# EFM8_Tag-Connect.net
KiCad netlist of a schematic drawn in EAGLE
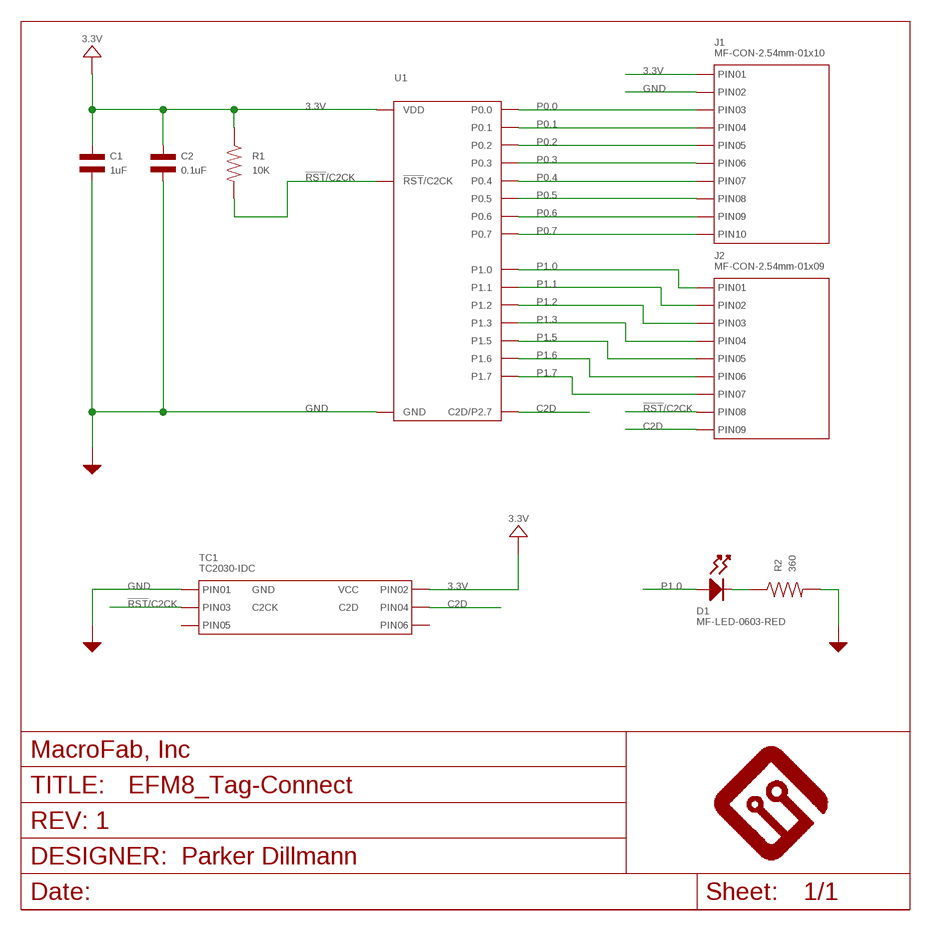
[diagram p0: schematic, sheet 1]

(export (version "E")
  (design (tool "Eeschema 10.0.6"))
  (components
    (comp (ref "C1")
      (value "1uF")
      (footprint "eagle-import:C0402")
      (fields (field (name "MPN") "MF-CAP-0402-1uF"))
      (libsource (lib "eagle-import") (part "CAPACITOR_NP_0402"))
    )
    (comp (ref "C2")
      (value "0.1uF")
      (footprint "eagle-import:C0402")
      (fields (field (name "MPN") "MF-CAP-0402-0.1uF"))
      (libsource (lib "eagle-import") (part "CAPACITOR_NP_0402"))
    )
    (comp (ref "D1")
      (value "MF-LED-0603-RED")
      (footprint "eagle-import:LED0603")
      (fields (field (name "HOUSEPART") "YES"))
      (libsource (lib "eagle-import") (part "LED_SINGLE-0603-RED"))
    )
    (comp (ref "FRAME1")
      (value "MF_FRAMEDEFAULT")
      (footprint "eagle-import:MF_FRAME_DEFAULT")
      (fields
        (field (name "HOUSEPART") "0")
        (field (name "DNAME") "Parker Dillmann")
        (field (name "REVNUM") "REV: 1")
      )
      (libsource (lib "eagle-import") (part "MF_FRAMEDEFAULT"))
    )
    (comp (ref "J1")
      (value "MF-CON-2.54mm-01x10")
      (footprint "eagle-import:PTH_2.54MM_01X10")
      (fields (field (name "HOUSEPART") "YES"))
      (libsource (lib "eagle-import") (part "CON_01X10_PTH_2.54MM"))
    )
    (comp (ref "J2")
      (value "MF-CON-2.54mm-01x09")
      (footprint "eagle-import:PTH_2.54MM_01X09")
      (fields (field (name "HOUSEPART") "YES"))
      (libsource (lib "eagle-import") (part "CON_01X09_PTH_2.54MM"))
    )
    (comp (ref "R1")
      (value "10K")
      (footprint "eagle-import:R0402")
      (fields (field (name "MPN") "MF-RES-0402-10K"))
      (libsource (lib "eagle-import") (part "RESISTOR_0402"))
    )
    (comp (ref "R2")
      (value "360")
      (footprint "eagle-import:R0402")
      (fields (field (name "MPN") "MF-RES-0402-360"))
      (libsource (lib "eagle-import") (part "RESISTOR_0402"))
    )
    (comp (ref "TC1")
      (value "TC2030-IDC")
      (footprint "eagle-import:TC2030-IDC-FP")
      (fields (field (name "HOUSEPART") "NO"))
      (libsource (lib "eagle-import") (part "CON_02X03_TC2030-IDC_SILABS2TC"))
    )
    (comp (ref "U1")
      (value "EFM8BB10F(2/4/8)G-A-QFN20")
      (footprint "eagle-import:EFM8BB10F(2_4_8)G-A-QFN20")
      (fields (field (name "HOUSEPART") "NO") (field (name "MPN") "EFM8BB10F2G-A-QFN20"))
      (libsource (lib "eagle-import") (part "EFM8BB10F(2/4/8)G-A-QFN20"))
    )
  )
  (nets
    (net (code "1") (name "/C2D") (class "Default")
      (node (ref "J2") (pin "P$9") (pinfunction "PIN9_P$9") (pintype "bidirectional"))
      (node (ref "TC1") (pin "P$4") (pinfunction "PIN4_P$4") (pintype "bidirectional"))
      (node (ref "U1") (pin "P$6") (pinfunction "C2D/P2.7_P$6") (pintype "bidirectional"))
    )
    (net (code "2") (name "/P0.0") (class "Default")
      (node (ref "J1") (pin "P$3") (pinfunction "PIN3_P$3") (pintype "bidirectional"))
      (node (ref "U1") (pin "P$2") (pinfunction "P0.0_P$2") (pintype "bidirectional"))
    )
    (net (code "3") (name "/P0.1") (class "Default")
      (node (ref "J1") (pin "P$4") (pinfunction "PIN4_P$4") (pintype "bidirectional"))
      (node (ref "U1") (pin "P$1") (pinfunction "P0.1_P$1") (pintype "bidirectional"))
    )
    (net (code "4") (name "/P0.2") (class "Default")
      (node (ref "J1") (pin "P$5") (pinfunction "PIN5_P$5") (pintype "bidirectional"))
      (node (ref "U1") (pin "P$20") (pinfunction "P0.2_P$20") (pintype "bidirectional"))
    )
    (net (code "5") (name "/P0.3") (class "Default")
      (node (ref "J1") (pin "P$6") (pinfunction "PIN6_P$6") (pintype "bidirectional"))
      (node (ref "U1") (pin "P$19") (pinfunction "P0.3_P$19") (pintype "bidirectional"))
    )
    (net (code "6") (name "/P0.4") (class "Default")
      (node (ref "J1") (pin "P$7") (pinfunction "PIN7_P$7") (pintype "bidirectional"))
      (node (ref "U1") (pin "P$18") (pinfunction "P0.4_P$18") (pintype "bidirectional"))
    )
    (net (code "7") (name "/P0.5") (class "Default")
      (node (ref "J1") (pin "P$8") (pinfunction "PIN8_P$8") (pintype "bidirectional"))
      (node (ref "U1") (pin "P$17") (pinfunction "P0.5_P$17") (pintype "bidirectional"))
    )
    (net (code "8") (name "/P0.6") (class "Default")
      (node (ref "J1") (pin "P$9") (pinfunction "PIN9_P$9") (pintype "bidirectional"))
      (node (ref "U1") (pin "P$16") (pinfunction "P0.6_P$16") (pintype "bidirectional"))
    )
    (net (code "9") (name "/P0.7") (class "Default")
      (node (ref "J1") (pin "P$10") (pinfunction "PIN10_P$10") (pintype "bidirectional"))
      (node (ref "U1") (pin "P$15") (pinfunction "P0.7_P$15") (pintype "bidirectional"))
    )
    (net (code "10") (name "/P1.0") (class "Default")
      (node (ref "D1") (pin "ANODE") (pinfunction "ANODE_ANODE") (pintype "power_in"))
      (node (ref "J2") (pin "P$1") (pinfunction "PIN1_P$1") (pintype "bidirectional"))
      (node (ref "U1") (pin "P$14") (pinfunction "P1.0_P$14") (pintype "bidirectional"))
    )
    (net (code "11") (name "/P1.1") (class "Default")
      (node (ref "J2") (pin "P$2") (pinfunction "PIN2_P$2") (pintype "bidirectional"))
      (node (ref "U1") (pin "P$13") (pinfunction "P1.1_P$13") (pintype "bidirectional"))
    )
    (net (code "12") (name "/P1.2") (class "Default")
      (node (ref "J2") (pin "P$3") (pinfunction "PIN3_P$3") (pintype "bidirectional"))
      (node (ref "U1") (pin "P$11") (pinfunction "P1.2_P$11") (pintype "bidirectional"))
    )
    (net (code "13") (name "/P1.3") (class "Default")
      (node (ref "J2") (pin "P$4") (pinfunction "PIN4_P$4") (pintype "bidirectional"))
      (node (ref "U1") (pin "P$10") (pinfunction "P1.3_P$10") (pintype "bidirectional"))
    )
    (net (code "14") (name "/P1.5") (class "Default")
      (node (ref "J2") (pin "P$5") (pinfunction "PIN5_P$5") (pintype "bidirectional"))
      (node (ref "U1") (pin "P$8") (pinfunction "P1.5_P$8") (pintype "bidirectional"))
    )
    (net (code "15") (name "/P1.6") (class "Default")
      (node (ref "J2") (pin "P$6") (pinfunction "PIN6_P$6") (pintype "bidirectional"))
      (node (ref "U1") (pin "P$7") (pinfunction "P1.6_P$7") (pintype "bidirectional"))
    )
    (net (code "16") (name "/P1.7") (class "Default")
      (node (ref "J2") (pin "P$7") (pinfunction "PIN7_P$7") (pintype "bidirectional"))
      (node (ref "U1") (pin "P$9") (pinfunction "P1.7_P$9") (pintype "bidirectional"))
    )
    (net (code "17") (name "/~{RST}{slash}C2CK") (class "Default")
      (node (ref "J2") (pin "P$8") (pinfunction "PIN8_P$8") (pintype "bidirectional"))
      (node (ref "R1") (pin "P$2") (pinfunction "P$2_P$2") (pintype "passive"))
      (node (ref "TC1") (pin "P$3") (pinfunction "PIN3_P$3") (pintype "bidirectional"))
      (node (ref "U1") (pin "P$5") (pinfunction "~{RST}/C2CK_P$5") (pintype "bidirectional"))
    )
    (net (code "18") (name "3.3V") (class "Default")
      (node (ref "C1") (pin "P$1") (pinfunction "P$1_P$1") (pintype "passive"))
      (node (ref "C2") (pin "P$1") (pinfunction "P$1_P$1") (pintype "passive"))
      (node (ref "J1") (pin "P$1") (pinfunction "PIN1_P$1") (pintype "bidirectional"))
      (node (ref "R1") (pin "P$1") (pinfunction "P$1_P$1") (pintype "passive"))
      (node (ref "TC1") (pin "P$2") (pinfunction "PIN2_P$2") (pintype "bidirectional"))
      (node (ref "U1") (pin "P$4") (pinfunction "VDD_P$4") (pintype "bidirectional"))
    )
    (net (code "19") (name "GND_RAIL") (class "Default")
      (node (ref "C1") (pin "P$2") (pinfunction "P$2_P$2") (pintype "passive"))
      (node (ref "C2") (pin "P$2") (pinfunction "P$2_P$2") (pintype "passive"))
      (node (ref "J1") (pin "P$2") (pinfunction "PIN2_P$2") (pintype "bidirectional"))
      (node (ref "R2") (pin "P$2") (pinfunction "P$2_P$2") (pintype "passive"))
      (node (ref "TC1") (pin "P$1") (pinfunction "PIN1_P$1") (pintype "bidirectional"))
      (node (ref "U1") (pin "P$12") (pinfunction "GND_P$12") (pintype "bidirectional"))
      (node (ref "U1") (pin "P$3") (pinfunction "GND_P$3") (pintype "bidirectional"))
      (node (ref "U1") (pin "PAD") (pinfunction "GND_PAD") (pintype "bidirectional"))
    )
    (net (code "20") (name "Net-(D1-PadCATHODE)") (class "Default")
      (node (ref "D1") (pin "CATHODE") (pinfunction "CATHODE_CATHODE") (pintype "power_in"))
      (node (ref "R2") (pin "P$1") (pinfunction "P$1_P$1") (pintype "passive"))
    )
    (net (code "21") (name "unconnected-(TC1-PIN5-PadP$5)") (class "Default")
      (node (ref "TC1") (pin "P$5") (pinfunction "PIN5_P$5") (pintype "bidirectional"))
    )
    (net (code "22") (name "unconnected-(TC1-PIN6-PadP$6)") (class "Default")
      (node (ref "TC1") (pin "P$6") (pinfunction "PIN6_P$6") (pintype "bidirectional"))
    )
  )
)
